# DPPXHK_10CL010_GRAPHICS.net
KiCad netlist of a schematic drawn in Altium Designer
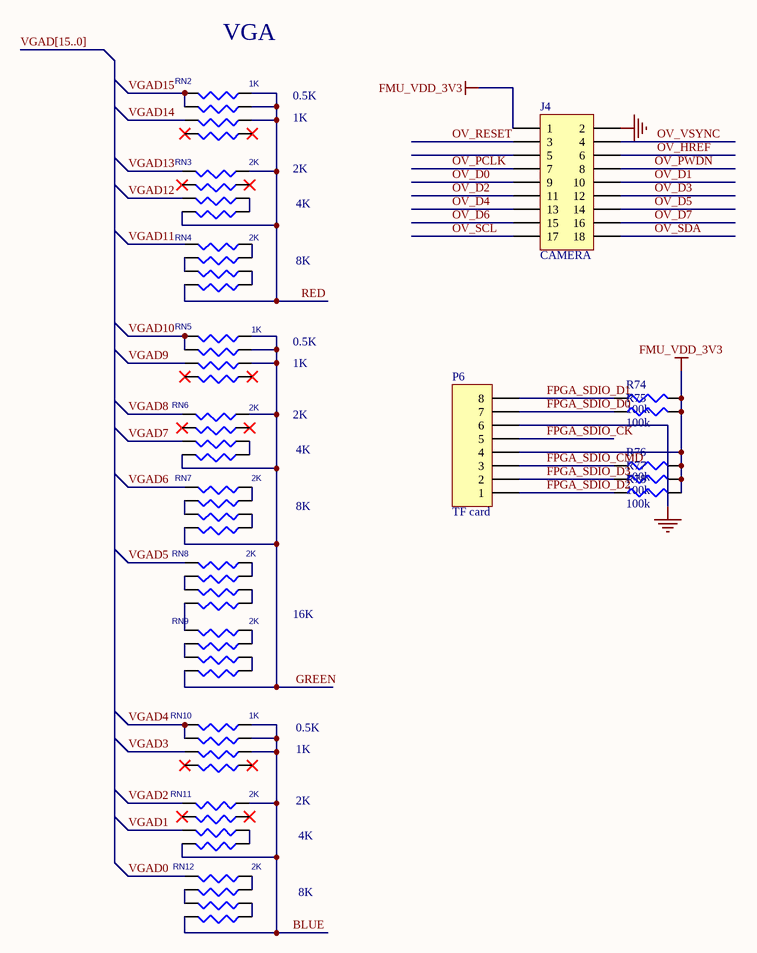
[diagram p0: DPPXHK_10CL010_GRAPHICS.SchDoc]

(export (version "E")
  (design (tool "Eeschema 10.0.6"))
  (components
    (comp (ref "J4")
      (value "CAMERA")
      (footprint "FPC-0.5-18")
      (description "Header, 9-Pin, Dual row")
      (fields (field (name "PUBLISHER") "Altium Limited"))
      (libsource (lib "Miscellaneous Connectors") (part "Header 9X2"))
    )
    (comp (ref "P6")
      (value "TF card")
      (footprint "TF-2")
      (description "Header, 8-Pin")
      (fields (field (name "PUBLISHER") "Altium Limited"))
      (libsource (lib "Miscellaneous Connectors") (part "Header 8"))
    )
    (comp (ref "R74")
      (value "100k")
      (footprint "0402R")
      (description "Resistor")
      (fields (field (name "PUBLISHER") "Altium Limited"))
      (libsource (lib "Miscellaneous Devices") (part "Res3"))
    )
    (comp (ref "R75")
      (value "100k")
      (footprint "0402R")
      (description "Resistor")
      (fields (field (name "PUBLISHER") "Altium Limited"))
      (libsource (lib "Miscellaneous Devices") (part "Res3"))
    )
    (comp (ref "R76")
      (value "100k")
      (footprint "0402R")
      (description "Resistor")
      (fields (field (name "PUBLISHER") "Altium Limited"))
      (libsource (lib "Miscellaneous Devices") (part "Res3"))
    )
    (comp (ref "R77")
      (value "100k")
      (footprint "0402R")
      (description "Resistor")
      (fields (field (name "PUBLISHER") "Altium Limited"))
      (libsource (lib "Miscellaneous Devices") (part "Res3"))
    )
    (comp (ref "R78")
      (value "100k")
      (footprint "0402R")
      (description "Resistor")
      (fields (field (name "PUBLISHER") "Altium Limited"))
      (libsource (lib "Miscellaneous Devices") (part "Res3"))
    )
    (comp (ref "RN2") (value "1K") (footprint "RN-8P") (libsource (lib "*") (part "RN_Dup1")))
    (comp (ref "RN3") (value "2K") (footprint "RN-8P") (libsource (lib "*") (part "RN_Dup1")))
    (comp (ref "RN4") (value "2K") (footprint "RN-8P") (libsource (lib "*") (part "RN_Dup1")))
    (comp (ref "RN5") (value "1K") (footprint "RN-8P") (libsource (lib "*") (part "RN_Dup1")))
    (comp (ref "RN6") (value "2K") (footprint "RN-8P") (libsource (lib "*") (part "RN_Dup1")))
    (comp (ref "RN7") (value "2K") (footprint "RN-8P") (libsource (lib "*") (part "RN_Dup1")))
    (comp (ref "RN8") (value "2K") (footprint "RN-8P") (libsource (lib "*") (part "RN_Dup1")))
    (comp (ref "RN9") (value "2K") (footprint "RN-8P") (libsource (lib "*") (part "RN_Dup1")))
    (comp (ref "RN10") (value "1K") (footprint "RN-8P") (libsource (lib "*") (part "RN_Dup1")))
    (comp (ref "RN11") (value "2K") (footprint "RN-8P") (libsource (lib "*") (part "RN_Dup1")))
    (comp (ref "RN12") (value "2K") (footprint "RN-8P") (libsource (lib "*") (part "RN_Dup1")))
  )
  (nets
    (net (code "1") (name "/BLUE") (class "Default")
      (node (ref "RN10") (pin "2") (pinfunction "2_2") (pintype "passive"))
      (node (ref "RN10") (pin "3") (pinfunction "3_3") (pintype "passive"))
      (node (ref "RN10") (pin "4") (pinfunction "4_4") (pintype "passive"))
      (node (ref "RN11") (pin "4") (pinfunction "4_4") (pintype "passive"))
      (node (ref "RN11") (pin "8") (pinfunction "8_8") (pintype "passive"))
      (node (ref "RN12") (pin "8") (pinfunction "8_8") (pintype "passive"))
    )
    (net (code "2") (name "/FPGA_SDIO_CK") (class "Default")
      (node (ref "P6") (pin "5") (pinfunction "5_5") (pintype "passive"))
    )
    (net (code "3") (name "/FPGA_SDIO_CMD") (class "Default")
      (node (ref "P6") (pin "3") (pinfunction "3_3") (pintype "passive"))
      (node (ref "R76") (pin "1") (pinfunction "1_1") (pintype "passive"))
    )
    (net (code "4") (name "/FPGA_SDIO_D0") (class "Default")
      (node (ref "P6") (pin "7") (pinfunction "7_7") (pintype "passive"))
      (node (ref "R75") (pin "1") (pinfunction "1_1") (pintype "passive"))
    )
    (net (code "5") (name "/FPGA_SDIO_D1") (class "Default")
      (node (ref "P6") (pin "8") (pinfunction "8_8") (pintype "passive"))
      (node (ref "R74") (pin "1") (pinfunction "1_1") (pintype "passive"))
    )
    (net (code "6") (name "/FPGA_SDIO_D2") (class "Default")
      (node (ref "P6") (pin "1") (pinfunction "1_1") (pintype "passive"))
      (node (ref "R78") (pin "1") (pinfunction "1_1") (pintype "passive"))
    )
    (net (code "7") (name "/FPGA_SDIO_D3") (class "Default")
      (node (ref "P6") (pin "2") (pinfunction "2_2") (pintype "passive"))
      (node (ref "R77") (pin "1") (pinfunction "1_1") (pintype "passive"))
    )
    (net (code "8") (name "/GREEN") (class "Default")
      (node (ref "RN5") (pin "2") (pinfunction "2_2") (pintype "passive"))
      (node (ref "RN5") (pin "3") (pinfunction "3_3") (pintype "passive"))
      (node (ref "RN5") (pin "4") (pinfunction "4_4") (pintype "passive"))
      (node (ref "RN6") (pin "4") (pinfunction "4_4") (pintype "passive"))
      (node (ref "RN6") (pin "8") (pinfunction "8_8") (pintype "passive"))
      (node (ref "RN7") (pin "8") (pinfunction "8_8") (pintype "passive"))
      (node (ref "RN9") (pin "8") (pinfunction "8_8") (pintype "passive"))
    )
    (net (code "9") (name "/OV_D0") (class "Default")
      (node (ref "J4") (pin "9") (pinfunction "9_9") (pintype "passive"))
    )
    (net (code "10") (name "/OV_D1") (class "Default")
      (node (ref "J4") (pin "10") (pinfunction "10_10") (pintype "passive"))
    )
    (net (code "11") (name "/OV_D2") (class "Default")
      (node (ref "J4") (pin "11") (pinfunction "11_11") (pintype "passive"))
    )
    (net (code "12") (name "/OV_D3") (class "Default")
      (node (ref "J4") (pin "12") (pinfunction "12_12") (pintype "passive"))
    )
    (net (code "13") (name "/OV_D4") (class "Default")
      (node (ref "J4") (pin "13") (pinfunction "13_13") (pintype "passive"))
    )
    (net (code "14") (name "/OV_D5") (class "Default")
      (node (ref "J4") (pin "14") (pinfunction "14_14") (pintype "passive"))
    )
    (net (code "15") (name "/OV_D6") (class "Default")
      (node (ref "J4") (pin "15") (pinfunction "15_15") (pintype "passive"))
    )
    (net (code "16") (name "/OV_D7") (class "Default")
      (node (ref "J4") (pin "16") (pinfunction "16_16") (pintype "passive"))
    )
    (net (code "17") (name "/OV_HREF") (class "Default")
      (node (ref "J4") (pin "6") (pinfunction "6_6") (pintype "passive"))
    )
    (net (code "18") (name "/OV_PCLK") (class "Default")
      (node (ref "J4") (pin "7") (pinfunction "7_7") (pintype "passive"))
    )
    (net (code "19") (name "/OV_PWDN") (class "Default")
      (node (ref "J4") (pin "8") (pinfunction "8_8") (pintype "passive"))
    )
    (net (code "20") (name "/OV_RESET") (class "Default")
      (node (ref "J4") (pin "3") (pinfunction "3_3") (pintype "passive"))
    )
    (net (code "21") (name "/OV_SCL") (class "Default")
      (node (ref "J4") (pin "17") (pinfunction "17_17") (pintype "passive"))
    )
    (net (code "22") (name "/OV_SDA") (class "Default")
      (node (ref "J4") (pin "18") (pinfunction "18_18") (pintype "passive"))
    )
    (net (code "23") (name "/OV_VSYNC") (class "Default")
      (node (ref "J4") (pin "4") (pinfunction "4_4") (pintype "passive"))
    )
    (net (code "24") (name "/RED") (class "Default")
      (node (ref "RN2") (pin "2") (pinfunction "2_2") (pintype "passive"))
      (node (ref "RN2") (pin "3") (pinfunction "3_3") (pintype "passive"))
      (node (ref "RN2") (pin "4") (pinfunction "4_4") (pintype "passive"))
      (node (ref "RN3") (pin "4") (pinfunction "4_4") (pintype "passive"))
      (node (ref "RN3") (pin "8") (pinfunction "8_8") (pintype "passive"))
      (node (ref "RN4") (pin "8") (pinfunction "8_8") (pintype "passive"))
    )
    (net (code "25") (name "/VGAD0") (class "Default")
      (node (ref "RN12") (pin "5") (pinfunction "5_5") (pintype "passive"))
    )
    (net (code "26") (name "/VGAD1") (class "Default")
      (node (ref "RN11") (pin "7") (pinfunction "7_7") (pintype "passive"))
    )
    (net (code "27") (name "/VGAD2") (class "Default")
      (node (ref "RN11") (pin "5") (pinfunction "5_5") (pintype "passive"))
    )
    (net (code "28") (name "/VGAD3") (class "Default")
      (node (ref "RN10") (pin "7") (pinfunction "7_7") (pintype "passive"))
    )
    (net (code "29") (name "/VGAD4") (class "Default")
      (node (ref "RN10") (pin "5") (pinfunction "5_5") (pintype "passive"))
      (node (ref "RN10") (pin "6") (pinfunction "6_6") (pintype "passive"))
    )
    (net (code "30") (name "/VGAD5") (class "Default")
      (node (ref "RN8") (pin "5") (pinfunction "5_5") (pintype "passive"))
    )
    (net (code "31") (name "/VGAD6") (class "Default")
      (node (ref "RN7") (pin "5") (pinfunction "5_5") (pintype "passive"))
    )
    (net (code "32") (name "/VGAD7") (class "Default")
      (node (ref "RN6") (pin "7") (pinfunction "7_7") (pintype "passive"))
    )
    (net (code "33") (name "/VGAD8") (class "Default")
      (node (ref "RN6") (pin "5") (pinfunction "5_5") (pintype "passive"))
    )
    (net (code "34") (name "/VGAD9") (class "Default")
      (node (ref "RN5") (pin "7") (pinfunction "7_7") (pintype "passive"))
    )
    (net (code "35") (name "/VGAD10") (class "Default")
      (node (ref "RN5") (pin "5") (pinfunction "5_5") (pintype "passive"))
      (node (ref "RN5") (pin "6") (pinfunction "6_6") (pintype "passive"))
    )
    (net (code "36") (name "/VGAD11") (class "Default")
      (node (ref "RN4") (pin "5") (pinfunction "5_5") (pintype "passive"))
    )
    (net (code "37") (name "/VGAD12") (class "Default")
      (node (ref "RN3") (pin "7") (pinfunction "7_7") (pintype "passive"))
    )
    (net (code "38") (name "/VGAD13") (class "Default")
      (node (ref "RN3") (pin "5") (pinfunction "5_5") (pintype "passive"))
    )
    (net (code "39") (name "/VGAD14") (class "Default")
      (node (ref "RN2") (pin "7") (pinfunction "7_7") (pintype "passive"))
    )
    (net (code "40") (name "/VGAD15") (class "Default")
      (node (ref "RN2") (pin "5") (pinfunction "5_5") (pintype "passive"))
      (node (ref "RN2") (pin "6") (pinfunction "6_6") (pintype "passive"))
    )
    (net (code "42") (name "FMU_VDD_3V3") (class "Default")
      (node (ref "J4") (pin "1") (pinfunction "1_1") (pintype "passive"))
      (node (ref "P6") (pin "4") (pinfunction "4_4") (pintype "passive"))
      (node (ref "R74") (pin "2") (pinfunction "2_2") (pintype "passive"))
      (node (ref "R75") (pin "2") (pinfunction "2_2") (pintype "passive"))
      (node (ref "R76") (pin "2") (pinfunction "2_2") (pintype "passive"))
      (node (ref "R77") (pin "2") (pinfunction "2_2") (pintype "passive"))
      (node (ref "R78") (pin "2") (pinfunction "2_2") (pintype "passive"))
    )
    (net (code "43") (name "GND") (class "Default")
      (node (ref "J4") (pin "2") (pinfunction "2_2") (pintype "passive"))
      (node (ref "P6") (pin "6") (pinfunction "6_6") (pintype "passive"))
    )
    (net (code "44") (name "Net-(RN3-Pad1)") (class "Default")
      (node (ref "RN3") (pin "1") (pinfunction "1_1") (pintype "passive"))
      (node (ref "RN3") (pin "2") (pinfunction "2_2") (pintype "passive"))
    )
    (net (code "45") (name "Net-(RN4-Pad1)") (class "Default")
      (node (ref "RN4") (pin "1") (pinfunction "1_1") (pintype "passive"))
      (node (ref "RN4") (pin "2") (pinfunction "2_2") (pintype "passive"))
    )
    (net (code "46") (name "Net-(RN4-Pad3)") (class "Default")
      (node (ref "RN4") (pin "3") (pinfunction "3_3") (pintype "passive"))
      (node (ref "RN4") (pin "4") (pinfunction "4_4") (pintype "passive"))
    )
    (net (code "47") (name "Net-(RN4-Pad6)") (class "Default")
      (node (ref "RN4") (pin "6") (pinfunction "6_6") (pintype "passive"))
      (node (ref "RN4") (pin "7") (pinfunction "7_7") (pintype "passive"))
    )
    (net (code "48") (name "Net-(RN6-Pad1)") (class "Default")
      (node (ref "RN6") (pin "1") (pinfunction "1_1") (pintype "passive"))
      (node (ref "RN6") (pin "2") (pinfunction "2_2") (pintype "passive"))
    )
    (net (code "49") (name "Net-(RN7-Pad1)") (class "Default")
      (node (ref "RN7") (pin "1") (pinfunction "1_1") (pintype "passive"))
      (node (ref "RN7") (pin "2") (pinfunction "2_2") (pintype "passive"))
    )
    (net (code "50") (name "Net-(RN7-Pad3)") (class "Default")
      (node (ref "RN7") (pin "3") (pinfunction "3_3") (pintype "passive"))
      (node (ref "RN7") (pin "4") (pinfunction "4_4") (pintype "passive"))
    )
    (net (code "51") (name "Net-(RN7-Pad6)") (class "Default")
      (node (ref "RN7") (pin "6") (pinfunction "6_6") (pintype "passive"))
      (node (ref "RN7") (pin "7") (pinfunction "7_7") (pintype "passive"))
    )
    (net (code "52") (name "Net-(RN8-Pad1)") (class "Default")
      (node (ref "RN8") (pin "1") (pinfunction "1_1") (pintype "passive"))
      (node (ref "RN8") (pin "2") (pinfunction "2_2") (pintype "passive"))
    )
    (net (code "53") (name "Net-(RN8-Pad3)") (class "Default")
      (node (ref "RN8") (pin "3") (pinfunction "3_3") (pintype "passive"))
      (node (ref "RN8") (pin "4") (pinfunction "4_4") (pintype "passive"))
    )
    (net (code "54") (name "Net-(RN8-Pad6)") (class "Default")
      (node (ref "RN8") (pin "6") (pinfunction "6_6") (pintype "passive"))
      (node (ref "RN8") (pin "7") (pinfunction "7_7") (pintype "passive"))
    )
    (net (code "55") (name "Net-(RN8-Pad8)") (class "Default")
      (node (ref "RN8") (pin "8") (pinfunction "8_8") (pintype "passive"))
      (node (ref "RN9") (pin "5") (pinfunction "5_5") (pintype "passive"))
    )
    (net (code "56") (name "Net-(RN9-Pad1)") (class "Default")
      (node (ref "RN9") (pin "1") (pinfunction "1_1") (pintype "passive"))
      (node (ref "RN9") (pin "2") (pinfunction "2_2") (pintype "passive"))
    )
    (net (code "57") (name "Net-(RN9-Pad3)") (class "Default")
      (node (ref "RN9") (pin "3") (pinfunction "3_3") (pintype "passive"))
      (node (ref "RN9") (pin "4") (pinfunction "4_4") (pintype "passive"))
    )
    (net (code "58") (name "Net-(RN9-Pad6)") (class "Default")
      (node (ref "RN9") (pin "6") (pinfunction "6_6") (pintype "passive"))
      (node (ref "RN9") (pin "7") (pinfunction "7_7") (pintype "passive"))
    )
    (net (code "59") (name "Net-(RN11-Pad1)") (class "Default")
      (node (ref "RN11") (pin "1") (pinfunction "1_1") (pintype "passive"))
      (node (ref "RN11") (pin "2") (pinfunction "2_2") (pintype "passive"))
    )
    (net (code "60") (name "Net-(RN12-Pad1)") (class "Default")
      (node (ref "RN12") (pin "1") (pinfunction "1_1") (pintype "passive"))
      (node (ref "RN12") (pin "2") (pinfunction "2_2") (pintype "passive"))
    )
    (net (code "61") (name "Net-(RN12-Pad3)") (class "Default")
      (node (ref "RN12") (pin "3") (pinfunction "3_3") (pintype "passive"))
      (node (ref "RN12") (pin "4") (pinfunction "4_4") (pintype "passive"))
    )
    (net (code "62") (name "Net-(RN12-Pad6)") (class "Default")
      (node (ref "RN12") (pin "6") (pinfunction "6_6") (pintype "passive"))
      (node (ref "RN12") (pin "7") (pinfunction "7_7") (pintype "passive"))
    )
    (net (code "63") (name "unconnected-(J4-Pad5)") (class "Default")
      (node (ref "J4") (pin "5") (pinfunction "5_5") (pintype "passive"))
    )
    (net (code "64") (name "unconnected-(RN2-Pad1)") (class "Default")
      (node (ref "RN2") (pin "1") (pinfunction "1_1") (pintype "passive+no_connect"))
    )
    (net (code "65") (name "unconnected-(RN2-Pad8)") (class "Default")
      (node (ref "RN2") (pin "8") (pinfunction "8_8") (pintype "passive+no_connect"))
    )
    (net (code "66") (name "unconnected-(RN3-Pad3)") (class "Default")
      (node (ref "RN3") (pin "3") (pinfunction "3_3") (pintype "passive+no_connect"))
    )
    (net (code "67") (name "unconnected-(RN3-Pad6)") (class "Default")
      (node (ref "RN3") (pin "6") (pinfunction "6_6") (pintype "passive+no_connect"))
    )
    (net (code "68") (name "unconnected-(RN5-Pad1)") (class "Default")
      (node (ref "RN5") (pin "1") (pinfunction "1_1") (pintype "passive+no_connect"))
    )
    (net (code "69") (name "unconnected-(RN5-Pad8)") (class "Default")
      (node (ref "RN5") (pin "8") (pinfunction "8_8") (pintype "passive+no_connect"))
    )
    (net (code "70") (name "unconnected-(RN6-Pad3)") (class "Default")
      (node (ref "RN6") (pin "3") (pinfunction "3_3") (pintype "passive+no_connect"))
    )
    (net (code "71") (name "unconnected-(RN6-Pad6)") (class "Default")
      (node (ref "RN6") (pin "6") (pinfunction "6_6") (pintype "passive+no_connect"))
    )
    (net (code "72") (name "unconnected-(RN10-Pad1)") (class "Default")
      (node (ref "RN10") (pin "1") (pinfunction "1_1") (pintype "passive+no_connect"))
    )
    (net (code "73") (name "unconnected-(RN10-Pad8)") (class "Default")
      (node (ref "RN10") (pin "8") (pinfunction "8_8") (pintype "passive+no_connect"))
    )
    (net (code "74") (name "unconnected-(RN11-Pad3)") (class "Default")
      (node (ref "RN11") (pin "3") (pinfunction "3_3") (pintype "passive+no_connect"))
    )
    (net (code "75") (name "unconnected-(RN11-Pad6)") (class "Default")
      (node (ref "RN11") (pin "6") (pinfunction "6_6") (pintype "passive+no_connect"))
    )
  )
)
